# eagle_2.net
KiCad netlist of a schematic drawn in EAGLE
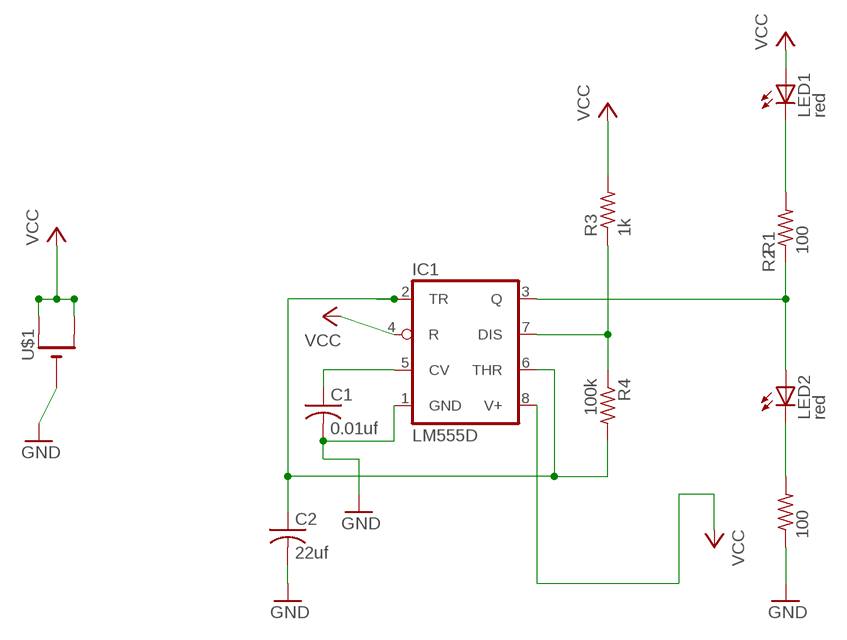
[diagram p0: schematic, sheet 1]

(export (version "E")
  (design (tool "Eeschema 10.0.6"))
  (components
    (comp (ref "C1")
      (value "0.01uf")
      (footprint "eagle-import:C0805")
      (libsource (lib "eagle-import") (part "C-USC0805"))
    )
    (comp (ref "C2")
      (value "22uf")
      (footprint "eagle-import:C0805")
      (libsource (lib "eagle-import") (part "C-USC0805"))
    )
    (comp (ref "IC1")
      (value "LM555D")
      (footprint "eagle-import:SO08")
      (libsource (lib "eagle-import") (part "555DLM"))
    )
    (comp (ref "LED1")
      (value "red")
      (footprint "eagle-import:CHIPLED_0805")
      (libsource (lib "eagle-import") (part "LEDCHIPLED_0805"))
    )
    (comp (ref "LED2")
      (value "red")
      (footprint "eagle-import:CHIPLED_0805")
      (libsource (lib "eagle-import") (part "LEDCHIPLED_0805"))
    )
    (comp (ref "R1")
      (value "100")
      (footprint "eagle-import:R0805")
      (libsource (lib "eagle-import") (part "R-US_R0805"))
    )
    (comp (ref "R2")
      (value "100")
      (footprint "eagle-import:R0805")
      (libsource (lib "eagle-import") (part "R-US_R0805"))
    )
    (comp (ref "R3")
      (value "1k")
      (footprint "eagle-import:R0805")
      (libsource (lib "eagle-import") (part "R-US_R0805"))
    )
    (comp (ref "R4")
      (value "100k")
      (footprint "eagle-import:R0805")
      (libsource (lib "eagle-import") (part "R-US_R0805"))
    )
    (comp (ref "U$1")
      (value "CR1220SMT")
      (footprint "eagle-import:CR1220-SMD")
      (libsource (lib "eagle-import") (part "CR1220SMT"))
    )
  )
  (nets
    (net (code "1") (name "GND") (class "Default")
      (node (ref "C1") (pin "2") (pinfunction "2_2") (pintype "passive"))
      (node (ref "C2") (pin "2") (pinfunction "2_2") (pintype "passive"))
      (node (ref "IC1") (pin "1") (pinfunction "GND_1") (pintype "power_in"))
      (node (ref "R2") (pin "1") (pinfunction "1_1") (pintype "passive"))
      (node (ref "U$1") (pin "-") (pinfunction "-_-") (pintype "passive"))
    )
    (net (code "2") (name "Net-(IC1-CV)") (class "Default")
      (node (ref "C1") (pin "1") (pinfunction "1_1") (pintype "passive"))
      (node (ref "IC1") (pin "5") (pinfunction "CV_5") (pintype "input"))
    )
    (net (code "3") (name "Net-(IC1-DIS)") (class "Default")
      (node (ref "IC1") (pin "7") (pinfunction "DIS_7") (pintype "input"))
      (node (ref "R3") (pin "1") (pinfunction "1_1") (pintype "passive"))
      (node (ref "R4") (pin "1") (pinfunction "1_1") (pintype "passive"))
    )
    (net (code "4") (name "Net-(IC1-Q)") (class "Default")
      (node (ref "IC1") (pin "3") (pinfunction "Q_3") (pintype "output"))
      (node (ref "LED2") (pin "A") (pinfunction "A_A") (pintype "passive"))
      (node (ref "R1") (pin "1") (pinfunction "1_1") (pintype "passive"))
    )
    (net (code "5") (name "Net-(IC1-THR)") (class "Default")
      (node (ref "C2") (pin "1") (pinfunction "1_1") (pintype "passive"))
      (node (ref "IC1") (pin "2") (pinfunction "TR_2") (pintype "input"))
      (node (ref "IC1") (pin "6") (pinfunction "THR_6") (pintype "input"))
      (node (ref "R4") (pin "2") (pinfunction "2_2") (pintype "passive"))
    )
    (net (code "6") (name "Net-(LED1-PadC)") (class "Default")
      (node (ref "LED1") (pin "C") (pinfunction "C_C") (pintype "passive"))
      (node (ref "R1") (pin "2") (pinfunction "2_2") (pintype "passive"))
    )
    (net (code "7") (name "Net-(LED2-PadC)") (class "Default")
      (node (ref "LED2") (pin "C") (pinfunction "C_C") (pintype "passive"))
      (node (ref "R2") (pin "2") (pinfunction "2_2") (pintype "passive"))
    )
    (net (code "8") (name "VCC") (class "Default")
      (node (ref "IC1") (pin "4") (pinfunction "R_4") (pintype "input"))
      (node (ref "IC1") (pin "8") (pinfunction "V+_8") (pintype "power_in"))
      (node (ref "LED1") (pin "A") (pinfunction "A_A") (pintype "passive"))
      (node (ref "R3") (pin "2") (pinfunction "2_2") (pintype "passive"))
      (node (ref "U$1") (pin "+$1") (pinfunction "+_+$1") (pintype "passive"))
      (node (ref "U$1") (pin "+$2") (pinfunction "+1_+$2") (pintype "passive"))
    )
  )
)
